# RcTransmitterMC.net
KiCad netlist of a schematic drawn in Altium Designer
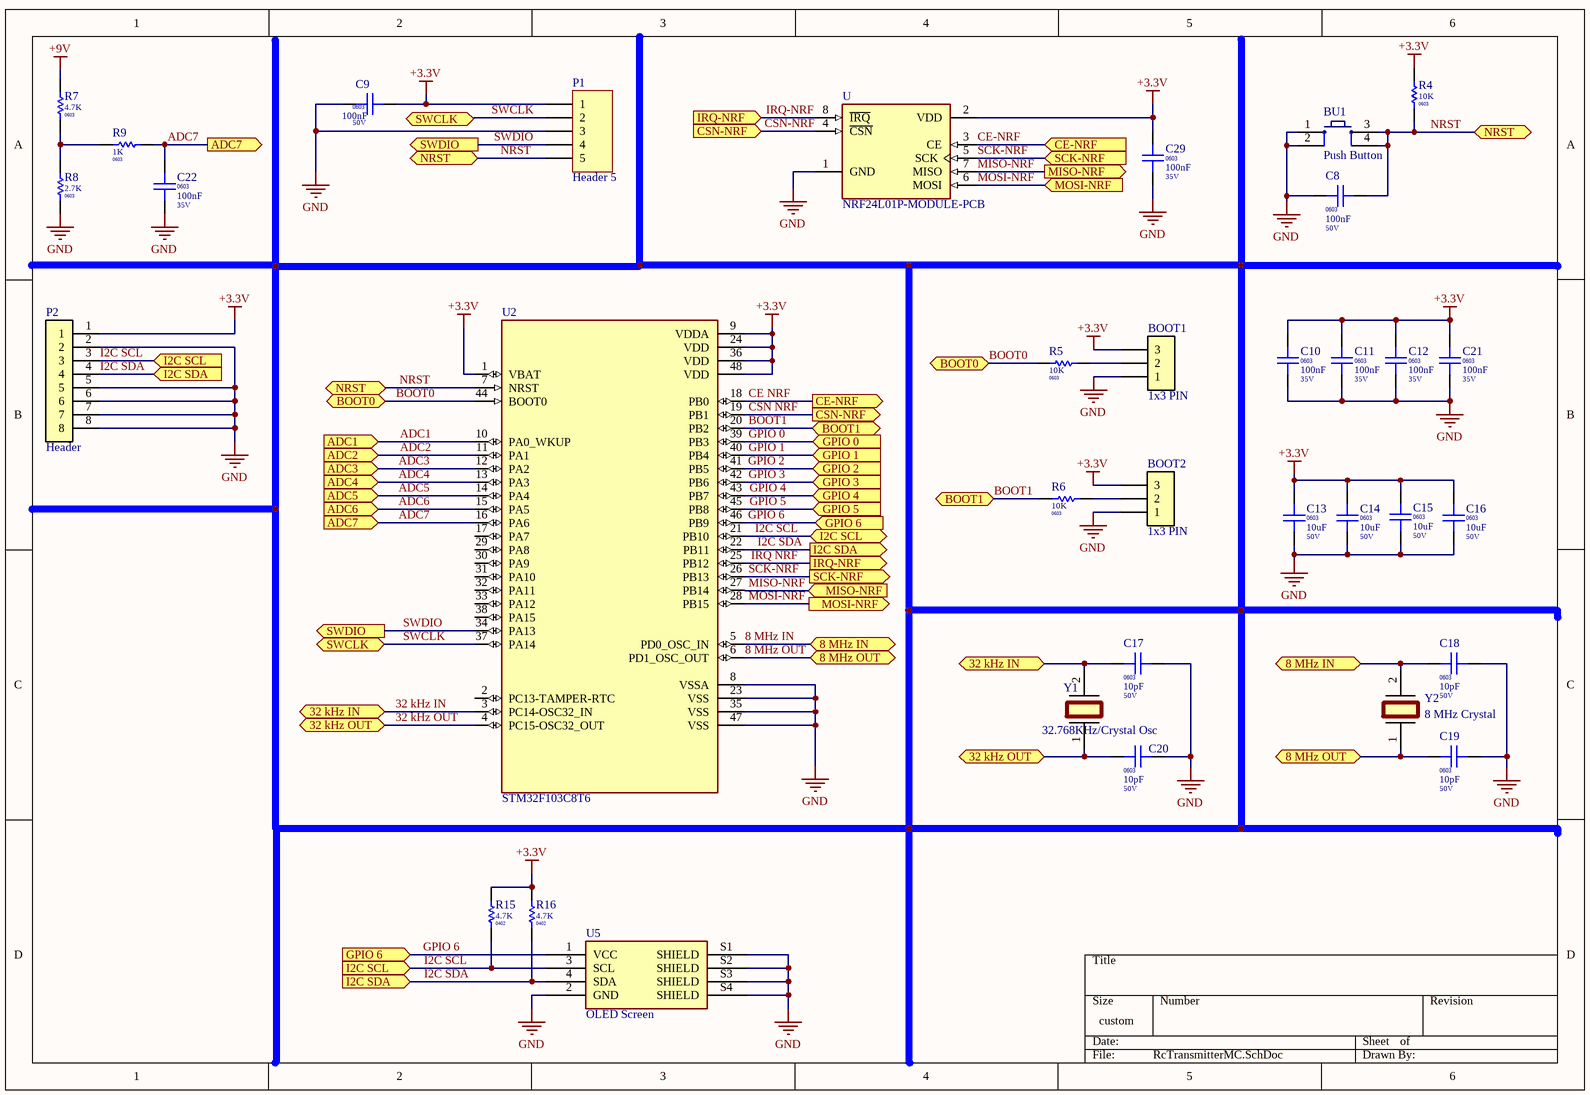
[diagram p0: RcTransmitterMC.SchDoc]

(export (version "E")
  (design (tool "Eeschema 10.0.6"))
  (components
    (comp (ref "BOOT1")
      (value "1x3 PIN")
      (footprint "HDR_2.54_1X3")
      (description "Header 2.54 1x3")
      (fields (field (name "PART NUMBER") "Connector0009"))
      (libsource (lib "AESK Database Library") (part "1x3 PIN"))
    )
    (comp (ref "BOOT2")
      (value "1x3 PIN")
      (footprint "HDR_2.54_1X3")
      (description "Header 2.54 1x3")
      (fields (field (name "PART NUMBER") "Connector0009"))
      (libsource (lib "AESK Database Library") (part "1x3 PIN"))
    )
    (comp (ref "BU1")
      (value "Push Button")
      (footprint "button son")
      (description "Smd Push Button")
      (libsource (lib "RcTransmitterSchlib1") (part "Push Button"))
    )
    (comp (ref "C8")
      (value "100nF")
      (footprint "CAPC 0603")
      (description "Capacitor Ceramic 100nF 50V 0603")
      (fields
        (field (name "TOLERANCE") "%10")
        (field (name "PACKAGE / CASE") "0603")
        (field (name "VOLTAGE") "50V")
        (field (name "PART NUMBER") "CAPC0285")
      )
      (libsource (lib "AESK Database Library") (part "NPCapacitor"))
    )
    (comp (ref "C9")
      (value "100nF")
      (footprint "CAPC 0603")
      (description "Capacitor Ceramic 100nF 50V 0603")
      (fields
        (field (name "TOLERANCE") "%10")
        (field (name "PACKAGE / CASE") "0603")
        (field (name "VOLTAGE") "50V")
        (field (name "PART NUMBER") "CAPC0285")
      )
      (libsource (lib "AESK Database Library") (part "NPCapacitor"))
    )
    (comp (ref "C10")
      (value "100nF")
      (footprint "CAPC 0603")
      (description "Capacitor Ceramic 100nF 35V 0603")
      (fields
        (field (name "TOLERANCE") "%10")
        (field (name "PACKAGE / CASE") "0603")
        (field (name "VOLTAGE") "35V")
        (field (name "PART NUMBER") "CAPC0328")
      )
      (libsource (lib "AESK Database Library") (part "NPCapacitor"))
    )
    (comp (ref "C11")
      (value "100nF")
      (footprint "CAPC 0603")
      (description "Capacitor Ceramic 100nF 35V 0603")
      (fields
        (field (name "TOLERANCE") "%10")
        (field (name "PACKAGE / CASE") "0603")
        (field (name "VOLTAGE") "35V")
        (field (name "PART NUMBER") "CAPC0328")
      )
      (libsource (lib "AESK Database Library") (part "NPCapacitor"))
    )
    (comp (ref "C12")
      (value "100nF")
      (footprint "CAPC 0603")
      (description "Capacitor Ceramic 100nF 35V 0603")
      (fields
        (field (name "TOLERANCE") "%10")
        (field (name "PACKAGE / CASE") "0603")
        (field (name "VOLTAGE") "35V")
        (field (name "PART NUMBER") "CAPC0328")
      )
      (libsource (lib "AESK Database Library") (part "NPCapacitor"))
    )
    (comp (ref "C13")
      (value "10uF")
      (footprint "CAPC 0603")
      (description "Capacitor Ceramic 10uF 50V 0603")
      (fields
        (field (name "TOLERANCE") "%10")
        (field (name "PACKAGE / CASE") "0603")
        (field (name "VOLTAGE") "50V")
        (field (name "PART NUMBER") "CAPC0301")
      )
      (libsource (lib "AESK Database Library") (part "NPCapacitor"))
    )
    (comp (ref "C14")
      (value "10uF")
      (footprint "CAPC 0603")
      (description "Capacitor Ceramic 10uF 50V 0603")
      (fields
        (field (name "TOLERANCE") "%10")
        (field (name "PACKAGE / CASE") "0603")
        (field (name "VOLTAGE") "50V")
        (field (name "PART NUMBER") "CAPC0301")
      )
      (libsource (lib "AESK Database Library") (part "NPCapacitor"))
    )
    (comp (ref "C15")
      (value "10uF")
      (footprint "CAPC 0603")
      (description "Capacitor Ceramic 10uF 50V 0603")
      (fields
        (field (name "TOLERANCE") "%10")
        (field (name "PACKAGE / CASE") "0603")
        (field (name "VOLTAGE") "50V")
        (field (name "PART NUMBER") "CAPC0301")
      )
      (libsource (lib "AESK Database Library") (part "NPCapacitor"))
    )
    (comp (ref "C16")
      (value "10uF")
      (footprint "CAPC 0603")
      (description "Capacitor Ceramic 10uF 50V 0603")
      (fields
        (field (name "TOLERANCE") "%10")
        (field (name "PACKAGE / CASE") "0603")
        (field (name "VOLTAGE") "50V")
        (field (name "PART NUMBER") "CAPC0301")
      )
      (libsource (lib "AESK Database Library") (part "NPCapacitor"))
    )
    (comp (ref "C17")
      (value "10pF")
      (footprint "CAPC 0603")
      (description "Capacitor Ceramic 10pF 50V 0603")
      (fields
        (field (name "TOLERANCE") "%10")
        (field (name "PACKAGE / CASE") "0603")
        (field (name "VOLTAGE") "50V")
        (field (name "PART NUMBER") "CAPC0242")
      )
      (libsource (lib "AESK Database Library") (part "NPCapacitor"))
    )
    (comp (ref "C18")
      (value "10pF")
      (footprint "CAPC 0603")
      (description "Capacitor Ceramic 10pF 50V 0603")
      (fields
        (field (name "TOLERANCE") "%10")
        (field (name "PACKAGE / CASE") "0603")
        (field (name "VOLTAGE") "50V")
        (field (name "PART NUMBER") "CAPC0242")
      )
      (libsource (lib "AESK Database Library") (part "NPCapacitor"))
    )
    (comp (ref "C19")
      (value "10pF")
      (footprint "CAPC 0603")
      (description "Capacitor Ceramic 10pF 50V 0603")
      (fields
        (field (name "TOLERANCE") "%10")
        (field (name "PACKAGE / CASE") "0603")
        (field (name "VOLTAGE") "50V")
        (field (name "PART NUMBER") "CAPC0242")
      )
      (libsource (lib "AESK Database Library") (part "NPCapacitor"))
    )
    (comp (ref "C20")
      (value "10pF")
      (footprint "CAPC 0603")
      (description "Capacitor Ceramic 10pF 50V 0603")
      (fields
        (field (name "TOLERANCE") "%10")
        (field (name "PACKAGE / CASE") "0603")
        (field (name "VOLTAGE") "50V")
        (field (name "PART NUMBER") "CAPC0242")
      )
      (libsource (lib "AESK Database Library") (part "NPCapacitor"))
    )
    (comp (ref "C21")
      (value "100nF")
      (footprint "CAPC 0603")
      (description "Capacitor Ceramic 100nF 35V 0603")
      (fields
        (field (name "TOLERANCE") "%10")
        (field (name "PACKAGE / CASE") "0603")
        (field (name "VOLTAGE") "35V")
        (field (name "PART NUMBER") "CAPC0328")
      )
      (libsource (lib "AESK Database Library") (part "NPCapacitor"))
    )
    (comp (ref "C22")
      (value "100nF")
      (footprint "CAPC 0603")
      (description "Capacitor Ceramic 100nF 35V 0603")
      (fields
        (field (name "TOLERANCE") "%10")
        (field (name "PACKAGE / CASE") "0603")
        (field (name "VOLTAGE") "35V")
        (field (name "PART NUMBER") "CAPC0328")
      )
      (libsource (lib "AESK Database Library") (part "NPCapacitor"))
    )
    (comp (ref "C29")
      (value "100nF")
      (footprint "CAPC 0603")
      (description "Capacitor Ceramic 100nF 35V 0603")
      (fields
        (field (name "TOLERANCE") "%10")
        (field (name "PACKAGE / CASE") "0603")
        (field (name "VOLTAGE") "35V")
        (field (name "PART NUMBER") "CAPC0328")
      )
      (libsource (lib "AESK Database Library") (part "NPCapacitor"))
    )
    (comp (ref "P1")
      (value "Header 5")
      (footprint "HDR1X5")
      (description "Header, 5-Pin")
      (fields (field (name "PUBLISHER") "Altium Limited"))
      (libsource (lib "Miscellaneous Connectors") (part "Header 5"))
    )
    (comp (ref "P2")
      (value "Header")
      (footprint "IMU_HEADER")
      (description "1x8")
      (libsource (lib "RcTransmitterSchlib1") (part "IMU_HEADER"))
    )
    (comp (ref "R4")
      (value "10K")
      (footprint "RESC 0603")
      (description "10K 0603")
      (fields
        (field (name "TOLERANCE") "%5")
        (field (name "POWER") "1/10W")
        (field (name "PACKAGE / CASE") "0603")
      )
      (libsource (lib "AESK Database Library") (part "Resistor"))
    )
    (comp (ref "R5")
      (value "10K")
      (footprint "RESC 0603")
      (description "10K 0603")
      (fields
        (field (name "TOLERANCE") "%5")
        (field (name "POWER") "1/10W")
        (field (name "PACKAGE / CASE") "0603")
      )
      (libsource (lib "AESK Database Library") (part "Resistor"))
    )
    (comp (ref "R6")
      (value "10K")
      (footprint "RESC 0603")
      (description "10K 0603")
      (fields
        (field (name "TOLERANCE") "%5")
        (field (name "POWER") "1/10W")
        (field (name "PACKAGE / CASE") "0603")
      )
      (libsource (lib "AESK Database Library") (part "Resistor"))
    )
    (comp (ref "R7")
      (value "4.7K")
      (footprint "RESC 0603")
      (description "4.7K 0603")
      (fields
        (field (name "TOLERANCE") "%5")
        (field (name "POWER") "1/10W")
        (field (name "PACKAGE / CASE") "0603")
      )
      (libsource (lib "AESK Database Library") (part "Resistor"))
    )
    (comp (ref "R8")
      (value "2.7K")
      (footprint "RESC 0603")
      (description "2.7K 0603")
      (fields
        (field (name "TOLERANCE") "%5")
        (field (name "POWER") "1/10W")
        (field (name "PACKAGE / CASE") "0603")
      )
      (libsource (lib "AESK Database Library") (part "Resistor"))
    )
    (comp (ref "R9")
      (value "1K")
      (footprint "RESC 0603")
      (description "1K 0603")
      (fields
        (field (name "TOLERANCE") "%5")
        (field (name "POWER") "1/10W")
        (field (name "PACKAGE / CASE") "0603")
      )
      (libsource (lib "AESK Database Library") (part "Resistor"))
    )
    (comp (ref "R15")
      (value "4.7K")
      (footprint "RESC 0402")
      (description "4.7K 0402")
      (fields
        (field (name "TOLERANCE") "%5")
        (field (name "POWER") "1/10W")
        (field (name "PACKAGE / CASE") "0402")
      )
      (libsource (lib "AESK Database Library") (part "Resistor"))
    )
    (comp (ref "R16")
      (value "4.7K")
      (footprint "RESC 0402")
      (description "4.7K 0402")
      (fields
        (field (name "TOLERANCE") "%5")
        (field (name "POWER") "1/10W")
        (field (name "PACKAGE / CASE") "0402")
      )
      (libsource (lib "AESK Database Library") (part "Resistor"))
    )
    (comp (ref "U")
      (value "NRF24L01P-MODULE-PCB")
      (footprint "nrf")
      (description "- Transceiver For Use With nRF24L01+")
      (fields (field (name "MF") "Nordic Semiconductor"))
      (libsource (lib "RcTransmitterSchlib1") (part "NRF24L01P-MODULE-PCB"))
    )
    (comp (ref "U2")
      (value "STM32F103C8T6")
      (footprint "QFP50P900X900X160-48N")
      (description "ARMÂ® CortexÂ®-M3 STM32F1 Microcontroller IC 32-Bit 72MHz 64KB _64K x 8_ FLASH")
      (fields (field (name "MF") "STMicroelectronics"))
      (libsource (lib "RcTransmitterSchlib1") (part "STM32F103C8T6"))
    )
    (comp (ref "U5")
      (value "OLED Screen")
      (footprint "SSD1106 OLED")
      (libsource (lib "RcTransmitterSchlib1") (part "SSD1106 OLED"))
    )
    (comp (ref "Y1")
      (value "32.768KHz/Crystal Osc")
      (footprint "32KhZ crystal oscillator")
      (description "Crystal or Oscillator")
      (libsource (lib "RcTransmitterSchlib1") (part "NX3215SA-32.768KHZ-EXS00A-MU00525"))
    )
    (comp (ref "Y2")
      (value "8 MHz Crystal")
      (footprint "XTAL_HC49P488W43L1085T450H368")
      (libsource (lib "RcTransmitterSchlib1") (part "XTAL_HC49P488W43L1085T450H368"))
    )
  )
  (nets
    (net (code "1") (name "+3.3V") (class "Default")
      (node (ref "BOOT1") (pin "3") (pinfunction "3_3") (pintype "passive"))
      (node (ref "BOOT2") (pin "3") (pinfunction "3_3") (pintype "passive"))
      (node (ref "C10") (pin "2") (pinfunction "2_2") (pintype "passive"))
      (node (ref "C11") (pin "2") (pinfunction "2_2") (pintype "passive"))
      (node (ref "C12") (pin "2") (pinfunction "2_2") (pintype "passive"))
      (node (ref "C13") (pin "2") (pinfunction "2_2") (pintype "passive"))
      (node (ref "C14") (pin "2") (pinfunction "2_2") (pintype "passive"))
      (node (ref "C15") (pin "2") (pinfunction "2_2") (pintype "passive"))
      (node (ref "C16") (pin "2") (pinfunction "2_2") (pintype "passive"))
      (node (ref "C21") (pin "2") (pinfunction "2_2") (pintype "passive"))
      (node (ref "C29") (pin "2") (pinfunction "2_2") (pintype "passive"))
      (node (ref "C9") (pin "2") (pinfunction "2_2") (pintype "passive"))
      (node (ref "P1") (pin "1") (pinfunction "1_1") (pintype "passive"))
      (node (ref "P2") (pin "1") (pinfunction "1_1") (pintype "passive"))
      (node (ref "R15") (pin "2") (pinfunction "2_2") (pintype "passive"))
      (node (ref "R16") (pin "2") (pinfunction "2_2") (pintype "passive"))
      (node (ref "R4") (pin "2") (pinfunction "2_2") (pintype "passive"))
      (node (ref "U") (pin "2") (pinfunction "VDD_2") (pintype "power_in"))
      (node (ref "U2") (pin "1") (pinfunction "VBAT_1") (pintype "bidirectional"))
      (node (ref "U2") (pin "24") (pinfunction "VDD_24") (pintype "power_in"))
      (node (ref "U2") (pin "36") (pinfunction "VDD_36") (pintype "power_in"))
      (node (ref "U2") (pin "48") (pinfunction "VDD_48") (pintype "power_in"))
      (node (ref "U2") (pin "9") (pinfunction "VDDA_9") (pintype "power_in"))
    )
    (net (code "2") (name "+9V") (class "Default")
      (node (ref "R7") (pin "2") (pinfunction "2_2") (pintype "passive"))
    )
    (net (code "3") (name "/8 MHz IN") (class "Default")
      (node (ref "C18") (pin "1") (pinfunction "1_1") (pintype "passive"))
      (node (ref "U2") (pin "5") (pinfunction "PD0_OSC_IN_5") (pintype "bidirectional"))
      (node (ref "Y2") (pin "2") (pintype "passive"))
    )
    (net (code "4") (name "/8 MHz OUT") (class "Default")
      (node (ref "C19") (pin "1") (pinfunction "1_1") (pintype "passive"))
      (node (ref "U2") (pin "6") (pinfunction "PD1_OSC_OUT_6") (pintype "bidirectional"))
      (node (ref "Y2") (pin "1") (pintype "passive"))
    )
    (net (code "5") (name "/32 kHz IN") (class "Default")
      (node (ref "C17") (pin "1") (pinfunction "1_1") (pintype "passive"))
      (node (ref "U2") (pin "3") (pinfunction "PC14-OSC32_IN_3") (pintype "bidirectional"))
      (node (ref "Y1") (pin "2") (pintype "passive"))
    )
    (net (code "6") (name "/32 kHz OUT") (class "Default")
      (node (ref "C20") (pin "1") (pinfunction "1_1") (pintype "passive"))
      (node (ref "U2") (pin "4") (pinfunction "PC15-OSC32_OUT_4") (pintype "bidirectional"))
      (node (ref "Y1") (pin "1") (pintype "passive"))
    )
    (net (code "7") (name "/ADC1") (class "Default")
      (node (ref "U2") (pin "10") (pinfunction "PA0_WKUP_10") (pintype "bidirectional"))
    )
    (net (code "8") (name "/ADC2") (class "Default")
      (node (ref "U2") (pin "11") (pinfunction "PA1_11") (pintype "bidirectional"))
    )
    (net (code "9") (name "/ADC3") (class "Default")
      (node (ref "U2") (pin "12") (pinfunction "PA2_12") (pintype "bidirectional"))
    )
    (net (code "10") (name "/ADC4") (class "Default")
      (node (ref "U2") (pin "13") (pinfunction "PA3_13") (pintype "bidirectional"))
    )
    (net (code "11") (name "/ADC5") (class "Default")
      (node (ref "U2") (pin "14") (pinfunction "PA4_14") (pintype "bidirectional"))
    )
    (net (code "12") (name "/ADC6") (class "Default")
      (node (ref "U2") (pin "15") (pinfunction "PA5_15") (pintype "bidirectional"))
    )
    (net (code "13") (name "/ADC7") (class "Default")
      (node (ref "C22") (pin "2") (pinfunction "2_2") (pintype "passive"))
      (node (ref "R9") (pin "2") (pinfunction "2_2") (pintype "passive"))
      (node (ref "U2") (pin "16") (pinfunction "PA6_16") (pintype "bidirectional"))
    )
    (net (code "14") (name "/BOOT0") (class "Default")
      (node (ref "R5") (pin "1") (pinfunction "1_1") (pintype "passive"))
      (node (ref "U2") (pin "44") (pinfunction "BOOT0_44") (pintype "input"))
    )
    (net (code "15") (name "/BOOT1") (class "Default")
      (node (ref "R6") (pin "1") (pinfunction "1_1") (pintype "passive"))
      (node (ref "U2") (pin "20") (pinfunction "PB2_20") (pintype "bidirectional"))
    )
    (net (code "16") (name "/CE NRF") (class "Default")
      (node (ref "U") (pin "3") (pinfunction "CE_3") (pintype "input"))
      (node (ref "U2") (pin "18") (pinfunction "PB0_18") (pintype "bidirectional"))
    )
    (net (code "17") (name "/CSN NRF") (class "Default")
      (node (ref "U") (pin "4") (pinfunction "~{CSN}_4") (pintype "input"))
      (node (ref "U2") (pin "19") (pinfunction "PB1_19") (pintype "bidirectional"))
    )
    (net (code "18") (name "/GPIO 0") (class "Default")
      (node (ref "U2") (pin "39") (pinfunction "PB3_39") (pintype "bidirectional"))
    )
    (net (code "19") (name "/GPIO 1") (class "Default")
      (node (ref "U2") (pin "40") (pinfunction "PB4_40") (pintype "bidirectional"))
    )
    (net (code "20") (name "/GPIO 2") (class "Default")
      (node (ref "U2") (pin "41") (pinfunction "PB5_41") (pintype "bidirectional"))
    )
    (net (code "21") (name "/GPIO 3") (class "Default")
      (node (ref "U2") (pin "42") (pinfunction "PB6_42") (pintype "bidirectional"))
    )
    (net (code "22") (name "/GPIO 4") (class "Default")
      (node (ref "U2") (pin "43") (pinfunction "PB7_43") (pintype "bidirectional"))
    )
    (net (code "23") (name "/GPIO 5") (class "Default")
      (node (ref "U2") (pin "45") (pinfunction "PB8_45") (pintype "bidirectional"))
    )
    (net (code "24") (name "/GPIO 6") (class "Default")
      (node (ref "U2") (pin "46") (pinfunction "PB9_46") (pintype "bidirectional"))
      (node (ref "U5") (pin "1") (pinfunction "VCC_1") (pintype "passive"))
    )
    (net (code "25") (name "/I2C SCL") (class "Default")
      (node (ref "P2") (pin "3") (pinfunction "3_3") (pintype "passive"))
      (node (ref "R15") (pin "1") (pinfunction "1_1") (pintype "passive"))
      (node (ref "U2") (pin "21") (pinfunction "PB10_21") (pintype "bidirectional"))
      (node (ref "U5") (pin "3") (pinfunction "SCL_3") (pintype "passive"))
    )
    (net (code "26") (name "/I2C SDA") (class "Default")
      (node (ref "P2") (pin "4") (pinfunction "4_4") (pintype "passive"))
      (node (ref "R16") (pin "1") (pinfunction "1_1") (pintype "passive"))
      (node (ref "U2") (pin "22") (pinfunction "PB11_22") (pintype "bidirectional"))
      (node (ref "U5") (pin "4") (pinfunction "SDA_4") (pintype "passive"))
    )
    (net (code "27") (name "/IRQ NRF") (class "Default")
      (node (ref "U") (pin "8") (pinfunction "~{IRQ}_8") (pintype "input"))
      (node (ref "U2") (pin "25") (pinfunction "PB12_25") (pintype "bidirectional"))
    )
    (net (code "28") (name "/MISO-NRF") (class "Default")
      (node (ref "U") (pin "7") (pinfunction "MISO_7") (pintype "input"))
      (node (ref "U2") (pin "27") (pinfunction "PB14_27") (pintype "bidirectional"))
    )
    (net (code "29") (name "/MOSI-NRF") (class "Default")
      (node (ref "U") (pin "6") (pinfunction "MOSI_6") (pintype "input"))
      (node (ref "U2") (pin "28") (pinfunction "PB15_28") (pintype "bidirectional"))
    )
    (net (code "30") (name "/NRST") (class "Default")
      (node (ref "BU1") (pin "3") (pinfunction "3_3") (pintype "passive"))
      (node (ref "BU1") (pin "4") (pinfunction "4_4") (pintype "passive"))
      (node (ref "C8") (pin "2") (pinfunction "2_2") (pintype "passive"))
      (node (ref "P1") (pin "5") (pinfunction "5_5") (pintype "passive"))
      (node (ref "R4") (pin "1") (pinfunction "1_1") (pintype "passive"))
      (node (ref "U2") (pin "7") (pinfunction "NRST_7") (pintype "input"))
    )
    (net (code "31") (name "/SCK-NRF") (class "Default")
      (node (ref "U") (pin "5") (pinfunction "SCK_5") (pintype "input"))
      (node (ref "U2") (pin "26") (pinfunction "PB13_26") (pintype "bidirectional"))
    )
    (net (code "32") (name "/SWCLK") (class "Default")
      (node (ref "P1") (pin "2") (pinfunction "2_2") (pintype "passive"))
      (node (ref "U2") (pin "37") (pinfunction "PA14_37") (pintype "bidirectional"))
    )
    (net (code "33") (name "/SWDIO") (class "Default")
      (node (ref "P1") (pin "4") (pinfunction "4_4") (pintype "passive"))
      (node (ref "U2") (pin "34") (pinfunction "PA13_34") (pintype "bidirectional"))
    )
    (net (code "34") (name "GND") (class "Default")
      (node (ref "BOOT1") (pin "1") (pinfunction "1_1") (pintype "passive"))
      (node (ref "BOOT2") (pin "1") (pinfunction "1_1") (pintype "passive"))
      (node (ref "BU1") (pin "1") (pinfunction "1_1") (pintype "passive"))
      (node (ref "BU1") (pin "2") (pinfunction "2_2") (pintype "passive"))
      (node (ref "C10") (pin "1") (pinfunction "1_1") (pintype "passive"))
      (node (ref "C11") (pin "1") (pinfunction "1_1") (pintype "passive"))
      (node (ref "C12") (pin "1") (pinfunction "1_1") (pintype "passive"))
      (node (ref "C13") (pin "1") (pinfunction "1_1") (pintype "passive"))
      (node (ref "C14") (pin "1") (pinfunction "1_1") (pintype "passive"))
      (node (ref "C15") (pin "1") (pinfunction "1_1") (pintype "passive"))
      (node (ref "C16") (pin "1") (pinfunction "1_1") (pintype "passive"))
      (node (ref "C17") (pin "2") (pinfunction "2_2") (pintype "passive"))
      (node (ref "C18") (pin "2") (pinfunction "2_2") (pintype "passive"))
      (node (ref "C19") (pin "2") (pinfunction "2_2") (pintype "passive"))
      (node (ref "C20") (pin "2") (pinfunction "2_2") (pintype "passive"))
      (node (ref "C21") (pin "1") (pinfunction "1_1") (pintype "passive"))
      (node (ref "C22") (pin "1") (pinfunction "1_1") (pintype "passive"))
      (node (ref "C29") (pin "1") (pinfunction "1_1") (pintype "passive"))
      (node (ref "C8") (pin "1") (pinfunction "1_1") (pintype "passive"))
      (node (ref "C9") (pin "1") (pinfunction "1_1") (pintype "passive"))
      (node (ref "P1") (pin "3") (pinfunction "3_3") (pintype "passive"))
      (node (ref "P2") (pin "2") (pinfunction "2_2") (pintype "passive"))
      (node (ref "P2") (pin "5") (pinfunction "5_5") (pintype "passive"))
      (node (ref "P2") (pin "6") (pinfunction "6_6") (pintype "passive"))
      (node (ref "P2") (pin "7") (pinfunction "7_7") (pintype "passive"))
      (node (ref "P2") (pin "8") (pinfunction "8_8") (pintype "passive"))
      (node (ref "R8") (pin "1") (pinfunction "1_1") (pintype "passive"))
      (node (ref "U") (pin "1") (pinfunction "GND_1") (pintype "power_in"))
      (node (ref "U2") (pin "23") (pinfunction "VSS_23") (pintype "power_in"))
      (node (ref "U2") (pin "35") (pinfunction "VSS_35") (pintype "power_in"))
      (node (ref "U2") (pin "47") (pinfunction "VSS_47") (pintype "power_in"))
      (node (ref "U2") (pin "8") (pinfunction "VSSA_8") (pintype "power_in"))
      (node (ref "U5") (pin "2") (pinfunction "GND_2") (pintype "passive"))
      (node (ref "U5") (pin "S1") (pinfunction "SHIELD_S1") (pintype "passive"))
      (node (ref "U5") (pin "S2") (pinfunction "SHIELD_S2") (pintype "passive"))
      (node (ref "U5") (pin "S3") (pinfunction "SHIELD_S3") (pintype "passive"))
      (node (ref "U5") (pin "S4") (pinfunction "SHIELD_S4") (pintype "passive"))
    )
    (net (code "35") (name "Net-(BOOT1-Pad2)") (class "Default")
      (node (ref "BOOT1") (pin "2") (pinfunction "2_2") (pintype "passive"))
      (node (ref "R5") (pin "2") (pinfunction "2_2") (pintype "passive"))
    )
    (net (code "36") (name "Net-(BOOT2-Pad2)") (class "Default")
      (node (ref "BOOT2") (pin "2") (pinfunction "2_2") (pintype "passive"))
      (node (ref "R6") (pin "2") (pinfunction "2_2") (pintype "passive"))
    )
    (net (code "37") (name "Net-(R7-Pad1)") (class "Default")
      (node (ref "R7") (pin "1") (pinfunction "1_1") (pintype "passive"))
      (node (ref "R8") (pin "2") (pinfunction "2_2") (pintype "passive"))
      (node (ref "R9") (pin "1") (pinfunction "1_1") (pintype "passive"))
    )
    (net (code "38") (name "unconnected-(U2-PA7-Pad17)") (class "Default")
      (node (ref "U2") (pin "17") (pinfunction "PA7_17") (pintype "bidirectional"))
    )
    (net (code "39") (name "unconnected-(U2-PA8-Pad29)") (class "Default")
      (node (ref "U2") (pin "29") (pinfunction "PA8_29") (pintype "bidirectional"))
    )
    (net (code "40") (name "unconnected-(U2-PA9-Pad30)") (class "Default")
      (node (ref "U2") (pin "30") (pinfunction "PA9_30") (pintype "bidirectional"))
    )
    (net (code "41") (name "unconnected-(U2-PA10-Pad31)") (class "Default")
      (node (ref "U2") (pin "31") (pinfunction "PA10_31") (pintype "bidirectional"))
    )
    (net (code "42") (name "unconnected-(U2-PA11-Pad32)") (class "Default")
      (node (ref "U2") (pin "32") (pinfunction "PA11_32") (pintype "bidirectional"))
    )
    (net (code "43") (name "unconnected-(U2-PA12-Pad33)") (class "Default")
      (node (ref "U2") (pin "33") (pinfunction "PA12_33") (pintype "bidirectional"))
    )
    (net (code "44") (name "unconnected-(U2-PA15-Pad38)") (class "Default")
      (node (ref "U2") (pin "38") (pinfunction "PA15_38") (pintype "bidirectional"))
    )
    (net (code "45") (name "unconnected-(U2-PC13-TAMPER-RTC-Pad2)") (class "Default")
      (node (ref "U2") (pin "2") (pinfunction "PC13-TAMPER-RTC_2") (pintype "bidirectional"))
    )
  )
)
